# dc32sao.net
KiCad netlist of a schematic drawn in EAGLE
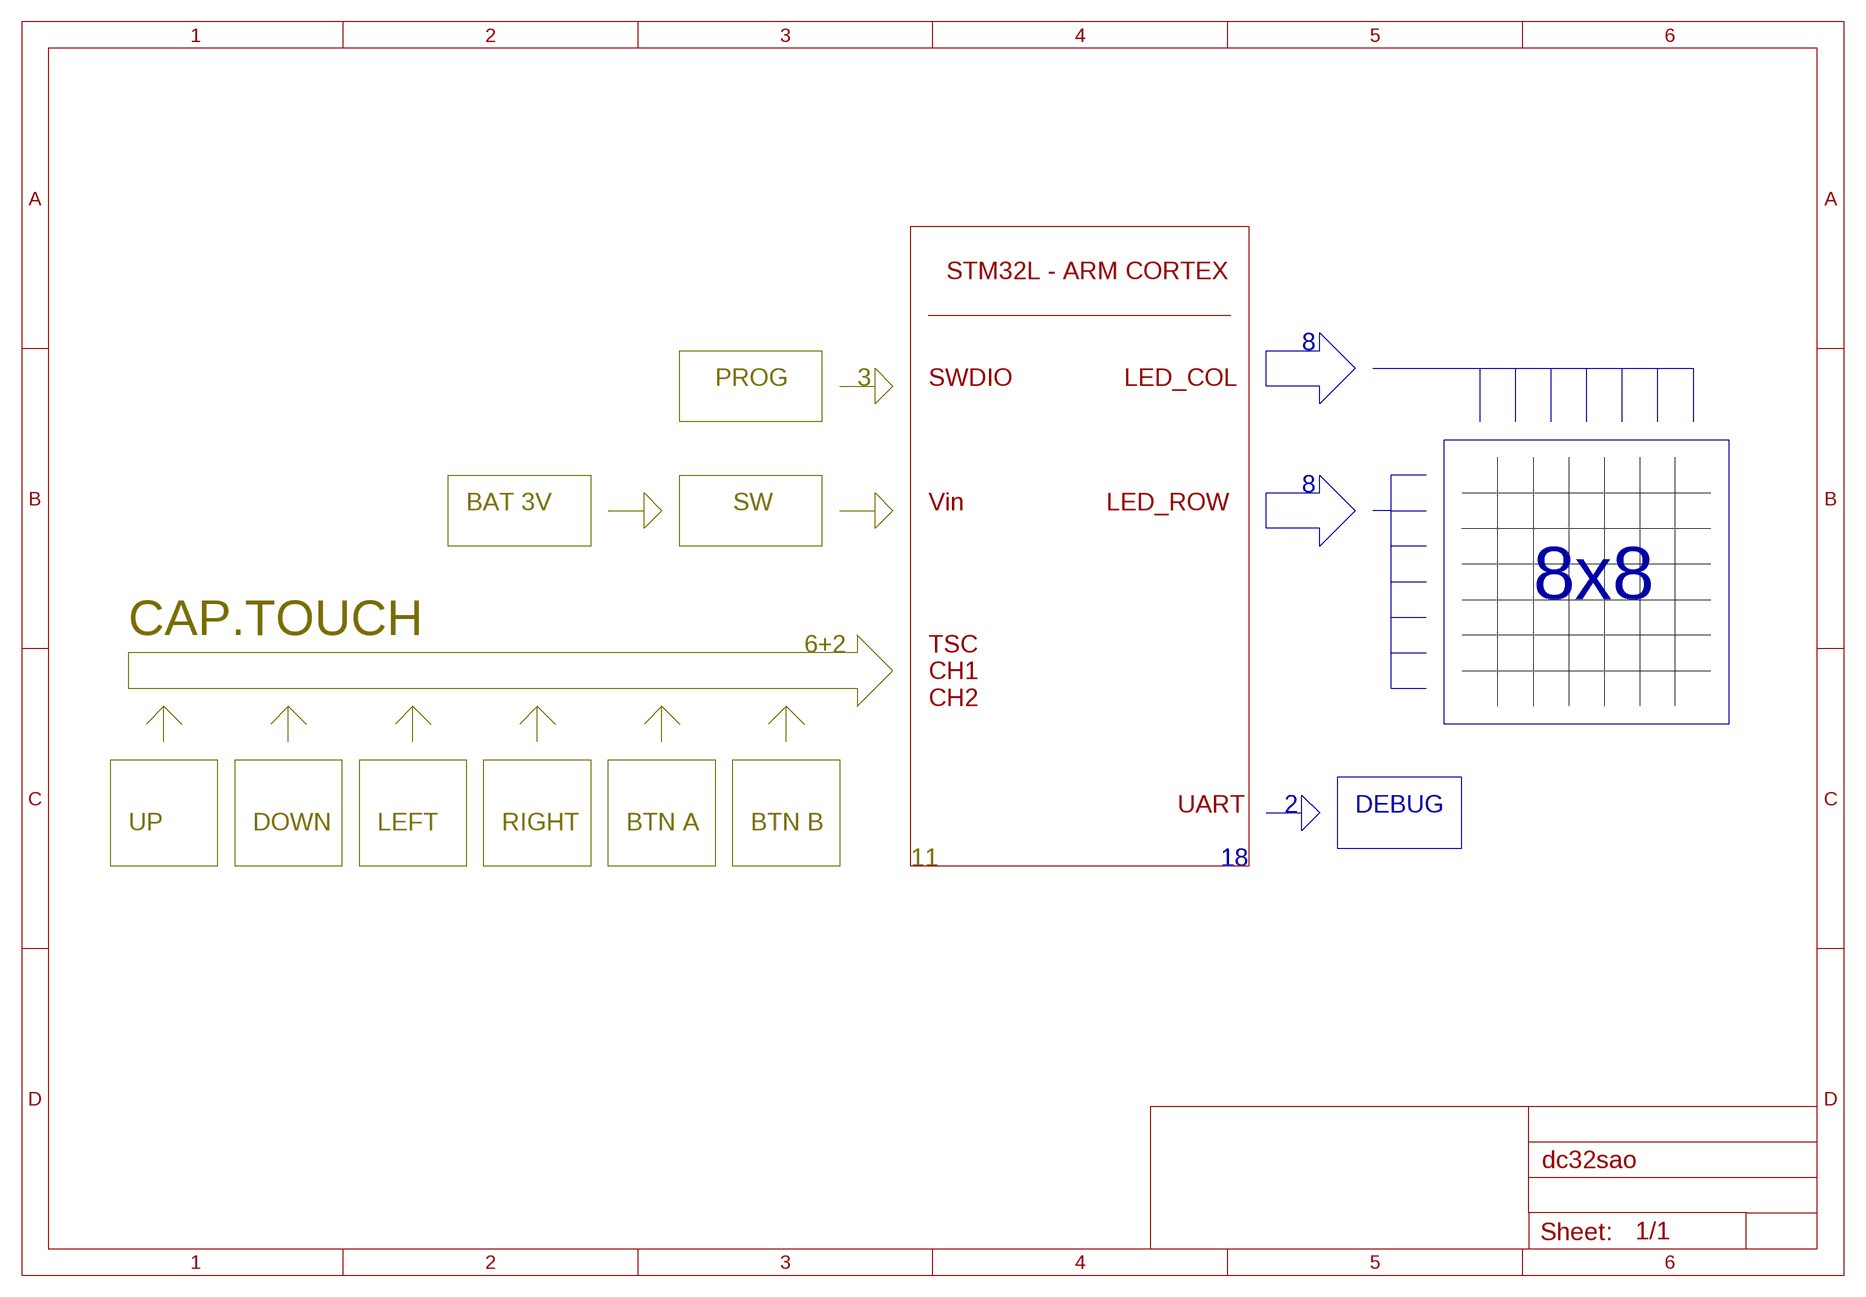
[diagram p0: schematic, sheet 1, part 1 of 2]
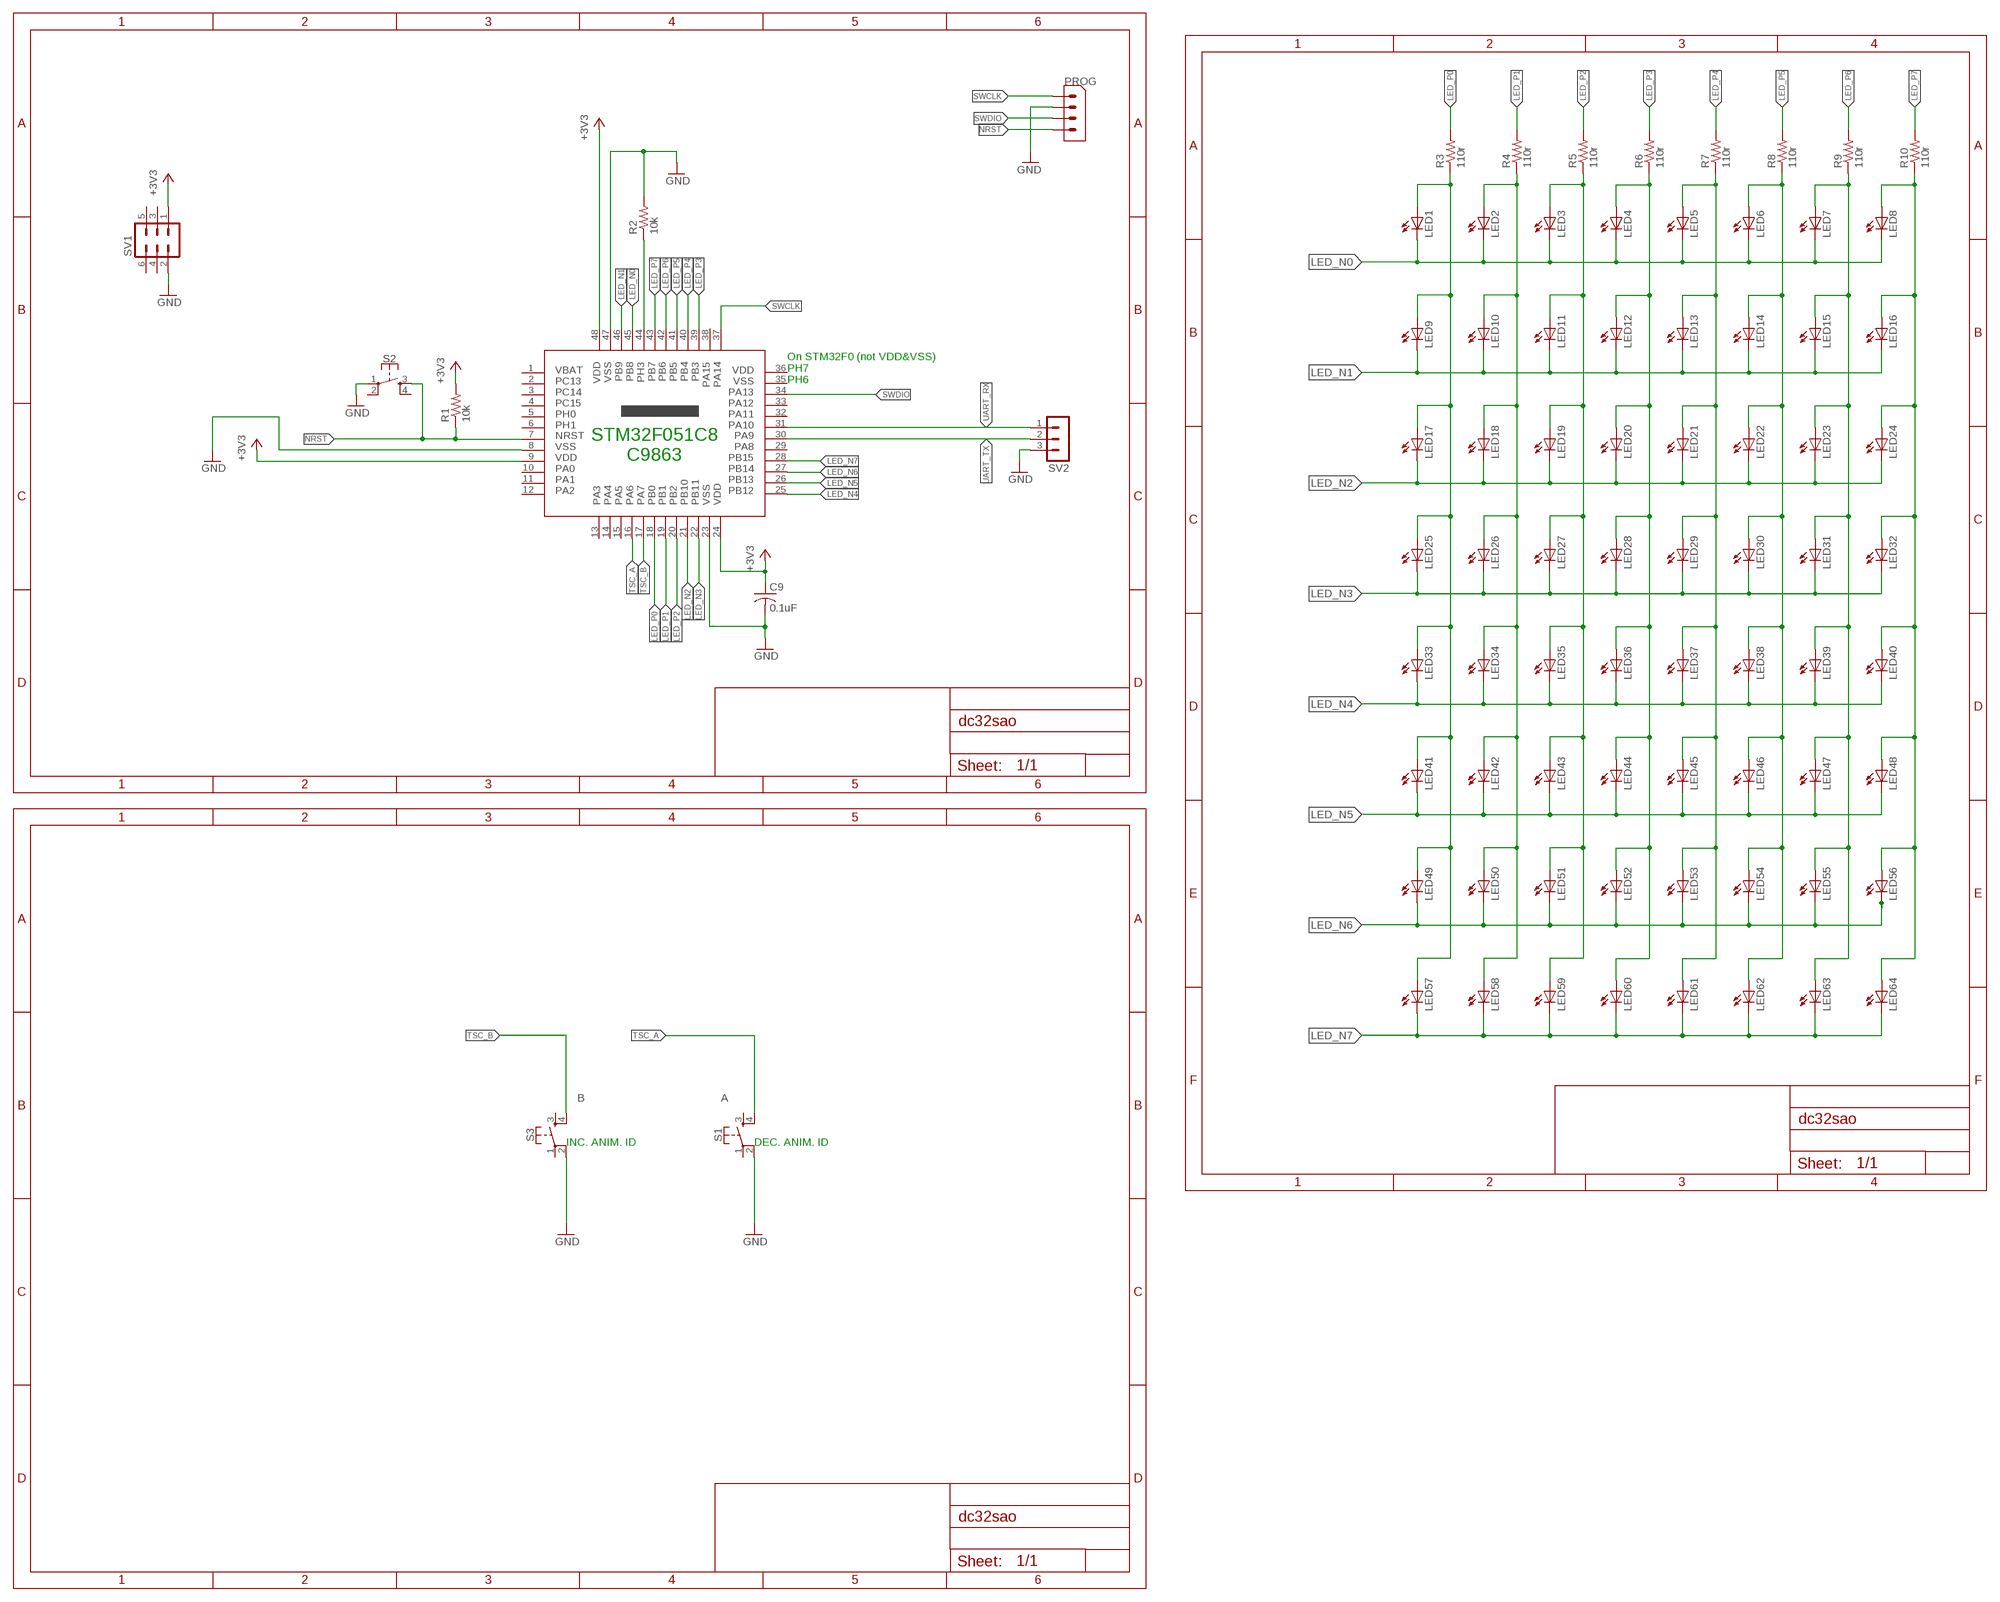
[diagram p1: schematic, sheet 1, part 2 of 2]

(export (version "E")
  (design (tool "Eeschema 10.0.6"))
  (components
    (comp (ref "C9")
      (value "0.1uF")
      (footprint "eagle-import:C0603")
      (libsource (lib "eagle-import") (part "C-USC0603"))
    )
    (comp (ref "LED1")
      (value "LEDCHIP-LED0603")
      (footprint "eagle-import:CHIP-LED0603")
      (libsource (lib "eagle-import") (part "LEDCHIP-LED0603"))
    )
    (comp (ref "LED2")
      (value "LEDCHIP-LED0603")
      (footprint "eagle-import:CHIP-LED0603")
      (libsource (lib "eagle-import") (part "LEDCHIP-LED0603"))
    )
    (comp (ref "LED3")
      (value "LEDCHIP-LED0603")
      (footprint "eagle-import:CHIP-LED0603")
      (libsource (lib "eagle-import") (part "LEDCHIP-LED0603"))
    )
    (comp (ref "LED4")
      (value "LEDCHIP-LED0603")
      (footprint "eagle-import:CHIP-LED0603")
      (libsource (lib "eagle-import") (part "LEDCHIP-LED0603"))
    )
    (comp (ref "LED5")
      (value "LEDCHIP-LED0603")
      (footprint "eagle-import:CHIP-LED0603")
      (libsource (lib "eagle-import") (part "LEDCHIP-LED0603"))
    )
    (comp (ref "LED6")
      (value "LEDCHIP-LED0603")
      (footprint "eagle-import:CHIP-LED0603")
      (libsource (lib "eagle-import") (part "LEDCHIP-LED0603"))
    )
    (comp (ref "LED7")
      (value "LEDCHIP-LED0603")
      (footprint "eagle-import:CHIP-LED0603")
      (libsource (lib "eagle-import") (part "LEDCHIP-LED0603"))
    )
    (comp (ref "LED8")
      (value "LEDCHIP-LED0603")
      (footprint "eagle-import:CHIP-LED0603")
      (libsource (lib "eagle-import") (part "LEDCHIP-LED0603"))
    )
    (comp (ref "LED9")
      (value "LEDCHIP-LED0603")
      (footprint "eagle-import:CHIP-LED0603")
      (libsource (lib "eagle-import") (part "LEDCHIP-LED0603"))
    )
    (comp (ref "LED10")
      (value "LEDCHIP-LED0603")
      (footprint "eagle-import:CHIP-LED0603")
      (libsource (lib "eagle-import") (part "LEDCHIP-LED0603"))
    )
    (comp (ref "LED11")
      (value "LEDCHIP-LED0603")
      (footprint "eagle-import:CHIP-LED0603")
      (libsource (lib "eagle-import") (part "LEDCHIP-LED0603"))
    )
    (comp (ref "LED12")
      (value "LEDCHIP-LED0603")
      (footprint "eagle-import:CHIP-LED0603")
      (libsource (lib "eagle-import") (part "LEDCHIP-LED0603"))
    )
    (comp (ref "LED13")
      (value "LEDCHIP-LED0603")
      (footprint "eagle-import:CHIP-LED0603")
      (libsource (lib "eagle-import") (part "LEDCHIP-LED0603"))
    )
    (comp (ref "LED14")
      (value "LEDCHIP-LED0603")
      (footprint "eagle-import:CHIP-LED0603")
      (libsource (lib "eagle-import") (part "LEDCHIP-LED0603"))
    )
    (comp (ref "LED15")
      (value "LEDCHIP-LED0603")
      (footprint "eagle-import:CHIP-LED0603")
      (libsource (lib "eagle-import") (part "LEDCHIP-LED0603"))
    )
    (comp (ref "LED16")
      (value "LEDCHIP-LED0603")
      (footprint "eagle-import:CHIP-LED0603")
      (libsource (lib "eagle-import") (part "LEDCHIP-LED0603"))
    )
    (comp (ref "LED17")
      (value "LEDCHIP-LED0603")
      (footprint "eagle-import:CHIP-LED0603")
      (libsource (lib "eagle-import") (part "LEDCHIP-LED0603"))
    )
    (comp (ref "LED18")
      (value "LEDCHIP-LED0603")
      (footprint "eagle-import:CHIP-LED0603")
      (libsource (lib "eagle-import") (part "LEDCHIP-LED0603"))
    )
    (comp (ref "LED19")
      (value "LEDCHIP-LED0603")
      (footprint "eagle-import:CHIP-LED0603")
      (libsource (lib "eagle-import") (part "LEDCHIP-LED0603"))
    )
    (comp (ref "LED20")
      (value "LEDCHIP-LED0603")
      (footprint "eagle-import:CHIP-LED0603")
      (libsource (lib "eagle-import") (part "LEDCHIP-LED0603"))
    )
    (comp (ref "LED21")
      (value "LEDCHIP-LED0603")
      (footprint "eagle-import:CHIP-LED0603")
      (libsource (lib "eagle-import") (part "LEDCHIP-LED0603"))
    )
    (comp (ref "LED22")
      (value "LEDCHIP-LED0603")
      (footprint "eagle-import:CHIP-LED0603")
      (libsource (lib "eagle-import") (part "LEDCHIP-LED0603"))
    )
    (comp (ref "LED23")
      (value "LEDCHIP-LED0603")
      (footprint "eagle-import:CHIP-LED0603")
      (libsource (lib "eagle-import") (part "LEDCHIP-LED0603"))
    )
    (comp (ref "LED24")
      (value "LEDCHIP-LED0603")
      (footprint "eagle-import:CHIP-LED0603")
      (libsource (lib "eagle-import") (part "LEDCHIP-LED0603"))
    )
    (comp (ref "LED25")
      (value "LEDCHIP-LED0603")
      (footprint "eagle-import:CHIP-LED0603")
      (libsource (lib "eagle-import") (part "LEDCHIP-LED0603"))
    )
    (comp (ref "LED26")
      (value "LEDCHIP-LED0603")
      (footprint "eagle-import:CHIP-LED0603")
      (libsource (lib "eagle-import") (part "LEDCHIP-LED0603"))
    )
    (comp (ref "LED27")
      (value "LEDCHIP-LED0603")
      (footprint "eagle-import:CHIP-LED0603")
      (libsource (lib "eagle-import") (part "LEDCHIP-LED0603"))
    )
    (comp (ref "LED28")
      (value "LEDCHIP-LED0603")
      (footprint "eagle-import:CHIP-LED0603")
      (libsource (lib "eagle-import") (part "LEDCHIP-LED0603"))
    )
    (comp (ref "LED29")
      (value "LEDCHIP-LED0603")
      (footprint "eagle-import:CHIP-LED0603")
      (libsource (lib "eagle-import") (part "LEDCHIP-LED0603"))
    )
    (comp (ref "LED30")
      (value "LEDCHIP-LED0603")
      (footprint "eagle-import:CHIP-LED0603")
      (libsource (lib "eagle-import") (part "LEDCHIP-LED0603"))
    )
    (comp (ref "LED31")
      (value "LEDCHIP-LED0603")
      (footprint "eagle-import:CHIP-LED0603")
      (libsource (lib "eagle-import") (part "LEDCHIP-LED0603"))
    )
    (comp (ref "LED32")
      (value "LEDCHIP-LED0603")
      (footprint "eagle-import:CHIP-LED0603")
      (libsource (lib "eagle-import") (part "LEDCHIP-LED0603"))
    )
    (comp (ref "LED33")
      (value "LEDCHIP-LED0603")
      (footprint "eagle-import:CHIP-LED0603")
      (libsource (lib "eagle-import") (part "LEDCHIP-LED0603"))
    )
    (comp (ref "LED34")
      (value "LEDCHIP-LED0603")
      (footprint "eagle-import:CHIP-LED0603")
      (libsource (lib "eagle-import") (part "LEDCHIP-LED0603"))
    )
    (comp (ref "LED35")
      (value "LEDCHIP-LED0603")
      (footprint "eagle-import:CHIP-LED0603")
      (libsource (lib "eagle-import") (part "LEDCHIP-LED0603"))
    )
    (comp (ref "LED36")
      (value "LEDCHIP-LED0603")
      (footprint "eagle-import:CHIP-LED0603")
      (libsource (lib "eagle-import") (part "LEDCHIP-LED0603"))
    )
    (comp (ref "LED37")
      (value "LEDCHIP-LED0603")
      (footprint "eagle-import:CHIP-LED0603")
      (libsource (lib "eagle-import") (part "LEDCHIP-LED0603"))
    )
    (comp (ref "LED38")
      (value "LEDCHIP-LED0603")
      (footprint "eagle-import:CHIP-LED0603")
      (libsource (lib "eagle-import") (part "LEDCHIP-LED0603"))
    )
    (comp (ref "LED39")
      (value "LEDCHIP-LED0603")
      (footprint "eagle-import:CHIP-LED0603")
      (libsource (lib "eagle-import") (part "LEDCHIP-LED0603"))
    )
    (comp (ref "LED40")
      (value "LEDCHIP-LED0603")
      (footprint "eagle-import:CHIP-LED0603")
      (libsource (lib "eagle-import") (part "LEDCHIP-LED0603"))
    )
    (comp (ref "LED41")
      (value "LEDCHIP-LED0603")
      (footprint "eagle-import:CHIP-LED0603")
      (libsource (lib "eagle-import") (part "LEDCHIP-LED0603"))
    )
    (comp (ref "LED42")
      (value "LEDCHIP-LED0603")
      (footprint "eagle-import:CHIP-LED0603")
      (libsource (lib "eagle-import") (part "LEDCHIP-LED0603"))
    )
    (comp (ref "LED43")
      (value "LEDCHIP-LED0603")
      (footprint "eagle-import:CHIP-LED0603")
      (libsource (lib "eagle-import") (part "LEDCHIP-LED0603"))
    )
    (comp (ref "LED44")
      (value "LEDCHIP-LED0603")
      (footprint "eagle-import:CHIP-LED0603")
      (libsource (lib "eagle-import") (part "LEDCHIP-LED0603"))
    )
    (comp (ref "LED45")
      (value "LEDCHIP-LED0603")
      (footprint "eagle-import:CHIP-LED0603")
      (libsource (lib "eagle-import") (part "LEDCHIP-LED0603"))
    )
    (comp (ref "LED46")
      (value "LEDCHIP-LED0603")
      (footprint "eagle-import:CHIP-LED0603")
      (libsource (lib "eagle-import") (part "LEDCHIP-LED0603"))
    )
    (comp (ref "LED47")
      (value "LEDCHIP-LED0603")
      (footprint "eagle-import:CHIP-LED0603")
      (libsource (lib "eagle-import") (part "LEDCHIP-LED0603"))
    )
    (comp (ref "LED48")
      (value "LEDCHIP-LED0603")
      (footprint "eagle-import:CHIP-LED0603")
      (libsource (lib "eagle-import") (part "LEDCHIP-LED0603"))
    )
    (comp (ref "LED49")
      (value "LEDCHIP-LED0603")
      (footprint "eagle-import:CHIP-LED0603")
      (libsource (lib "eagle-import") (part "LEDCHIP-LED0603"))
    )
    (comp (ref "LED50")
      (value "LEDCHIP-LED0603")
      (footprint "eagle-import:CHIP-LED0603")
      (libsource (lib "eagle-import") (part "LEDCHIP-LED0603"))
    )
    (comp (ref "LED51")
      (value "LEDCHIP-LED0603")
      (footprint "eagle-import:CHIP-LED0603")
      (libsource (lib "eagle-import") (part "LEDCHIP-LED0603"))
    )
    (comp (ref "LED52")
      (value "LEDCHIP-LED0603")
      (footprint "eagle-import:CHIP-LED0603")
      (libsource (lib "eagle-import") (part "LEDCHIP-LED0603"))
    )
    (comp (ref "LED53")
      (value "LEDCHIP-LED0603")
      (footprint "eagle-import:CHIP-LED0603")
      (libsource (lib "eagle-import") (part "LEDCHIP-LED0603"))
    )
    (comp (ref "LED54")
      (value "LEDCHIP-LED0603")
      (footprint "eagle-import:CHIP-LED0603")
      (libsource (lib "eagle-import") (part "LEDCHIP-LED0603"))
    )
    (comp (ref "LED55")
      (value "LEDCHIP-LED0603")
      (footprint "eagle-import:CHIP-LED0603")
      (libsource (lib "eagle-import") (part "LEDCHIP-LED0603"))
    )
    (comp (ref "LED56")
      (value "LEDCHIP-LED0603")
      (footprint "eagle-import:CHIP-LED0603")
      (libsource (lib "eagle-import") (part "LEDCHIP-LED0603"))
    )
    (comp (ref "LED57")
      (value "LEDCHIP-LED0603")
      (footprint "eagle-import:CHIP-LED0603")
      (libsource (lib "eagle-import") (part "LEDCHIP-LED0603"))
    )
    (comp (ref "LED58")
      (value "LEDCHIP-LED0603")
      (footprint "eagle-import:CHIP-LED0603")
      (libsource (lib "eagle-import") (part "LEDCHIP-LED0603"))
    )
    (comp (ref "LED59")
      (value "LEDCHIP-LED0603")
      (footprint "eagle-import:CHIP-LED0603")
      (libsource (lib "eagle-import") (part "LEDCHIP-LED0603"))
    )
    (comp (ref "LED60")
      (value "LEDCHIP-LED0603")
      (footprint "eagle-import:CHIP-LED0603")
      (libsource (lib "eagle-import") (part "LEDCHIP-LED0603"))
    )
    (comp (ref "LED61")
      (value "LEDCHIP-LED0603")
      (footprint "eagle-import:CHIP-LED0603")
      (libsource (lib "eagle-import") (part "LEDCHIP-LED0603"))
    )
    (comp (ref "LED62")
      (value "LEDCHIP-LED0603")
      (footprint "eagle-import:CHIP-LED0603")
      (libsource (lib "eagle-import") (part "LEDCHIP-LED0603"))
    )
    (comp (ref "LED63")
      (value "LEDCHIP-LED0603")
      (footprint "eagle-import:CHIP-LED0603")
      (libsource (lib "eagle-import") (part "LEDCHIP-LED0603"))
    )
    (comp (ref "LED64")
      (value "LEDCHIP-LED0603")
      (footprint "eagle-import:CHIP-LED0603")
      (libsource (lib "eagle-import") (part "LEDCHIP-LED0603"))
    )
    (comp (ref "PROG")
      (value "4-PIN-1.25MM")
      (footprint "eagle-import:4-PIN-1.25MM")
      (libsource (lib "eagle-import") (part "4-PIN-1.25MM"))
    )
    (comp (ref "R1")
      (value "10k")
      (footprint "eagle-import:R0603")
      (libsource (lib "eagle-import") (part "R-US_R0603"))
    )
    (comp (ref "R2")
      (value "10k")
      (footprint "eagle-import:R0603")
      (libsource (lib "eagle-import") (part "R-US_R0603"))
    )
    (comp (ref "R3")
      (value "110r")
      (footprint "eagle-import:R0603")
      (libsource (lib "eagle-import") (part "R-US_R0603"))
    )
    (comp (ref "R4")
      (value "110r")
      (footprint "eagle-import:R0603")
      (libsource (lib "eagle-import") (part "R-US_R0603"))
    )
    (comp (ref "R5")
      (value "110r")
      (footprint "eagle-import:R0603")
      (libsource (lib "eagle-import") (part "R-US_R0603"))
    )
    (comp (ref "R6")
      (value "110r")
      (footprint "eagle-import:R0603")
      (libsource (lib "eagle-import") (part "R-US_R0603"))
    )
    (comp (ref "R7")
      (value "110r")
      (footprint "eagle-import:R0603")
      (libsource (lib "eagle-import") (part "R-US_R0603"))
    )
    (comp (ref "R8")
      (value "110r")
      (footprint "eagle-import:R0603")
      (libsource (lib "eagle-import") (part "R-US_R0603"))
    )
    (comp (ref "R9")
      (value "110r")
      (footprint "eagle-import:R0603")
      (libsource (lib "eagle-import") (part "R-US_R0603"))
    )
    (comp (ref "R10")
      (value "110r")
      (footprint "eagle-import:R0603")
      (libsource (lib "eagle-import") (part "R-US_R0603"))
    )
    (comp (ref "S1")
      (value "MOMENTARY-SWITCH-SPST-2-SMD-5.2MM")
      (footprint "eagle-import:TACTILE_SWITCH_SMD_5.2MM")
      (libsource (lib "eagle-import") (part "MOMENTARY-SWITCH-SPST-2-SMD-5.2MM"))
    )
    (comp (ref "S2")
      (value "MOMENTARY-SWITCH-SPST-2-SMD-5.2MM")
      (footprint "eagle-import:TACTILE_SWITCH_SMD_5.2MM")
      (libsource (lib "eagle-import") (part "MOMENTARY-SWITCH-SPST-2-SMD-5.2MM"))
    )
    (comp (ref "S3")
      (value "MOMENTARY-SWITCH-SPST-2-SMD-5.2MM")
      (footprint "eagle-import:TACTILE_SWITCH_SMD_5.2MM")
      (libsource (lib "eagle-import") (part "MOMENTARY-SWITCH-SPST-2-SMD-5.2MM"))
    )
    (comp (ref "SV1")
      (value "MA03-2")
      (footprint "eagle-import:MA03-2")
      (libsource (lib "eagle-import") (part "MA03-2"))
    )
    (comp (ref "SV2")
      (value "MA03-1")
      (footprint "eagle-import:MA03-1")
      (libsource (lib "eagle-import") (part "MA03-1"))
    )
    (comp (ref "U$2")
      (value "STM32L431CC")
      (footprint "eagle-import:QFP50P900X900X160-48")
      (libsource (lib "eagle-import") (part "STM32L431CC"))
    )
  )
  (nets
    (net (code "1") (name "+3V3") (class "Default")
      (node (ref "C9") (pin "1") (pinfunction "1_1") (pintype "passive"))
      (node (ref "R1") (pin "2") (pinfunction "2_2") (pintype "passive"))
      (node (ref "SV1") (pin "1") (pinfunction "1_1") (pintype "passive"))
      (node (ref "U$2") (pin "24") (pinfunction "P$24_24") (pintype "bidirectional"))
      (node (ref "U$2") (pin "48") (pinfunction "P$48_48") (pintype "bidirectional"))
      (node (ref "U$2") (pin "9") (pinfunction "P$9_9") (pintype "bidirectional"))
    )
    (net (code "2") (name "GND") (class "Default")
      (node (ref "C9") (pin "2") (pinfunction "2_2") (pintype "passive"))
      (node (ref "PROG") (pin "P$3") (pinfunction "2_P$3") (pintype "bidirectional"))
      (node (ref "R2") (pin "2") (pinfunction "2_2") (pintype "passive"))
      (node (ref "S1") (pin "2") (pinfunction "2_2") (pintype "passive"))
      (node (ref "S2") (pin "1") (pinfunction "1_1") (pintype "passive"))
      (node (ref "S3") (pin "2") (pinfunction "2_2") (pintype "passive"))
      (node (ref "SV1") (pin "2") (pinfunction "2_2") (pintype "passive"))
      (node (ref "SV2") (pin "3") (pinfunction "3_3") (pintype "passive"))
      (node (ref "U$2") (pin "23") (pinfunction "P$23_23") (pintype "bidirectional"))
      (node (ref "U$2") (pin "47") (pinfunction "P$47_47") (pintype "bidirectional"))
      (node (ref "U$2") (pin "8") (pinfunction "P$8_8") (pintype "bidirectional"))
    )
    (net (code "3") (name "LED_N0") (class "Default")
      (node (ref "LED1") (pin "C") (pinfunction "C_C") (pintype "passive"))
      (node (ref "LED2") (pin "C") (pinfunction "C_C") (pintype "passive"))
      (node (ref "LED3") (pin "C") (pinfunction "C_C") (pintype "passive"))
      (node (ref "LED4") (pin "C") (pinfunction "C_C") (pintype "passive"))
      (node (ref "LED5") (pin "C") (pinfunction "C_C") (pintype "passive"))
      (node (ref "LED6") (pin "C") (pinfunction "C_C") (pintype "passive"))
      (node (ref "LED7") (pin "C") (pinfunction "C_C") (pintype "passive"))
      (node (ref "LED8") (pin "C") (pinfunction "C_C") (pintype "passive"))
      (node (ref "U$2") (pin "45") (pinfunction "P$45_45") (pintype "bidirectional"))
    )
    (net (code "4") (name "LED_N1") (class "Default")
      (node (ref "LED10") (pin "C") (pinfunction "C_C") (pintype "passive"))
      (node (ref "LED11") (pin "C") (pinfunction "C_C") (pintype "passive"))
      (node (ref "LED12") (pin "C") (pinfunction "C_C") (pintype "passive"))
      (node (ref "LED13") (pin "C") (pinfunction "C_C") (pintype "passive"))
      (node (ref "LED14") (pin "C") (pinfunction "C_C") (pintype "passive"))
      (node (ref "LED15") (pin "C") (pinfunction "C_C") (pintype "passive"))
      (node (ref "LED16") (pin "C") (pinfunction "C_C") (pintype "passive"))
      (node (ref "LED9") (pin "C") (pinfunction "C_C") (pintype "passive"))
      (node (ref "U$2") (pin "46") (pinfunction "P$46_46") (pintype "bidirectional"))
    )
    (net (code "5") (name "LED_N2") (class "Default")
      (node (ref "LED17") (pin "C") (pinfunction "C_C") (pintype "passive"))
      (node (ref "LED18") (pin "C") (pinfunction "C_C") (pintype "passive"))
      (node (ref "LED19") (pin "C") (pinfunction "C_C") (pintype "passive"))
      (node (ref "LED20") (pin "C") (pinfunction "C_C") (pintype "passive"))
      (node (ref "LED21") (pin "C") (pinfunction "C_C") (pintype "passive"))
      (node (ref "LED22") (pin "C") (pinfunction "C_C") (pintype "passive"))
      (node (ref "LED23") (pin "C") (pinfunction "C_C") (pintype "passive"))
      (node (ref "LED24") (pin "C") (pinfunction "C_C") (pintype "passive"))
      (node (ref "U$2") (pin "21") (pinfunction "P$21_21") (pintype "bidirectional"))
    )
    (net (code "6") (name "LED_N3") (class "Default")
      (node (ref "LED25") (pin "C") (pinfunction "C_C") (pintype "passive"))
      (node (ref "LED26") (pin "C") (pinfunction "C_C") (pintype "passive"))
      (node (ref "LED27") (pin "C") (pinfunction "C_C") (pintype "passive"))
      (node (ref "LED28") (pin "C") (pinfunction "C_C") (pintype "passive"))
      (node (ref "LED29") (pin "C") (pinfunction "C_C") (pintype "passive"))
      (node (ref "LED30") (pin "C") (pinfunction "C_C") (pintype "passive"))
      (node (ref "LED31") (pin "C") (pinfunction "C_C") (pintype "passive"))
      (node (ref "LED32") (pin "C") (pinfunction "C_C") (pintype "passive"))
      (node (ref "U$2") (pin "22") (pinfunction "P$22_22") (pintype "bidirectional"))
    )
    (net (code "7") (name "LED_N4") (class "Default")
      (node (ref "LED33") (pin "C") (pinfunction "C_C") (pintype "passive"))
      (node (ref "LED34") (pin "C") (pinfunction "C_C") (pintype "passive"))
      (node (ref "LED35") (pin "C") (pinfunction "C_C") (pintype "passive"))
      (node (ref "LED36") (pin "C") (pinfunction "C_C") (pintype "passive"))
      (node (ref "LED37") (pin "C") (pinfunction "C_C") (pintype "passive"))
      (node (ref "LED38") (pin "C") (pinfunction "C_C") (pintype "passive"))
      (node (ref "LED39") (pin "C") (pinfunction "C_C") (pintype "passive"))
      (node (ref "LED40") (pin "C") (pinfunction "C_C") (pintype "passive"))
      (node (ref "U$2") (pin "25") (pinfunction "P$25_25") (pintype "bidirectional"))
    )
    (net (code "8") (name "LED_N5") (class "Default")
      (node (ref "LED41") (pin "C") (pinfunction "C_C") (pintype "passive"))
      (node (ref "LED42") (pin "C") (pinfunction "C_C") (pintype "passive"))
      (node (ref "LED43") (pin "C") (pinfunction "C_C") (pintype "passive"))
      (node (ref "LED44") (pin "C") (pinfunction "C_C") (pintype "passive"))
      (node (ref "LED45") (pin "C") (pinfunction "C_C") (pintype "passive"))
      (node (ref "LED46") (pin "C") (pinfunction "C_C") (pintype "passive"))
      (node (ref "LED47") (pin "C") (pinfunction "C_C") (pintype "passive"))
      (node (ref "LED48") (pin "C") (pinfunction "C_C") (pintype "passive"))
      (node (ref "U$2") (pin "26") (pinfunction "P$26_26") (pintype "bidirectional"))
    )
    (net (code "9") (name "LED_N6") (class "Default")
      (node (ref "LED49") (pin "C") (pinfunction "C_C") (pintype "passive"))
      (node (ref "LED50") (pin "C") (pinfunction "C_C") (pintype "passive"))
      (node (ref "LED51") (pin "C") (pinfunction "C_C") (pintype "passive"))
      (node (ref "LED52") (pin "C") (pinfunction "C_C") (pintype "passive"))
      (node (ref "LED53") (pin "C") (pinfunction "C_C") (pintype "passive"))
      (node (ref "LED54") (pin "C") (pinfunction "C_C") (pintype "passive"))
      (node (ref "LED55") (pin "C") (pinfunction "C_C") (pintype "passive"))
      (node (ref "LED56") (pin "C") (pinfunction "C_C") (pintype "passive"))
      (node (ref "U$2") (pin "27") (pinfunction "P$27_27") (pintype "bidirectional"))
    )
    (net (code "10") (name "LED_N7") (class "Default")
      (node (ref "LED57") (pin "C") (pinfunction "C_C") (pintype "passive"))
      (node (ref "LED58") (pin "C") (pinfunction "C_C") (pintype "passive"))
      (node (ref "LED59") (pin "C") (pinfunction "C_C") (pintype "passive"))
      (node (ref "LED60") (pin "C") (pinfunction "C_C") (pintype "passive"))
      (node (ref "LED61") (pin "C") (pinfunction "C_C") (pintype "passive"))
      (node (ref "LED62") (pin "C") (pinfunction "C_C") (pintype "passive"))
      (node (ref "LED63") (pin "C") (pinfunction "C_C") (pintype "passive"))
      (node (ref "LED64") (pin "C") (pinfunction "C_C") (pintype "passive"))
      (node (ref "U$2") (pin "28") (pinfunction "P$28_28") (pintype "bidirectional"))
    )
    (net (code "11") (name "LED_P0") (class "Default")
      (node (ref "R3") (pin "2") (pinfunction "2_2") (pintype "passive"))
      (node (ref "U$2") (pin "18") (pinfunction "P$18_18") (pintype "bidirectional"))
    )
    (net (code "12") (name "LED_P1") (class "Default")
      (node (ref "R4") (pin "2") (pinfunction "2_2") (pintype "passive"))
      (node (ref "U$2") (pin "19") (pinfunction "P$19_19") (pintype "bidirectional"))
    )
    (net (code "13") (name "LED_P2") (class "Default")
      (node (ref "R5") (pin "2") (pinfunction "2_2") (pintype "passive"))
      (node (ref "U$2") (pin "20") (pinfunction "P$20_20") (pintype "bidirectional"))
    )
    (net (code "14") (name "LED_P3") (class "Default")
      (node (ref "R6") (pin "2") (pinfunction "2_2") (pintype "passive"))
      (node (ref "U$2") (pin "39") (pinfunction "P$39_39") (pintype "bidirectional"))
    )
    (net (code "15") (name "LED_P4") (class "Default")
      (node (ref "R7") (pin "2") (pinfunction "2_2") (pintype "passive"))
      (node (ref "U$2") (pin "40") (pinfunction "P$40_40") (pintype "bidirectional"))
    )
    (net (code "16") (name "LED_P5") (class "Default")
      (node (ref "R8") (pin "2") (pinfunction "2_2") (pintype "passive"))
      (node (ref "U$2") (pin "41") (pinfunction "P$41_41") (pintype "bidirectional"))
    )
    (net (code "17") (name "LED_P6") (class "Default")
      (node (ref "R9") (pin "2") (pinfunction "2_2") (pintype "passive"))
      (node (ref "U$2") (pin "42") (pinfunction "P$42_42") (pintype "bidirectional"))
    )
    (net (code "18") (name "LED_P7") (class "Default")
      (node (ref "R10") (pin "2") (pinfunction "2_2") (pintype "passive"))
      (node (ref "U$2") (pin "43") (pinfunction "P$43_43") (pintype "bidirectional"))
    )
    (net (code "19") (name "NRST") (class "Default")
      (node (ref "PROG") (pin "P$1") (pinfunction "4_P$1") (pintype "bidirectional"))
      (node (ref "R1") (pin "1") (pinfunction "1_1") (pintype "passive"))
      (node (ref "S2") (pin "3") (pinfunction "3_3") (pintype "passive"))
      (node (ref "U$2") (pin "7") (pinfunction "P$7_7") (pintype "bidirectional"))
    )
    (net (code "20") (name "Net-(LED1-PadA)") (class "Default")
      (node (ref "LED1") (pin "A") (pinfunction "A_A") (pintype "passive"))
      (node (ref "LED17") (pin "A") (pinfunction "A_A") (pintype "passive"))
      (node (ref "LED25") (pin "A") (pinfunction "A_A") (pintype "passive"))
      (node (ref "LED33") (pin "A") (pinfunction "A_A") (pintype "passive"))
      (node (ref "LED41") (pin "A") (pinfunction "A_A") (pintype "passive"))
      (node (ref "LED49") (pin "A") (pinfunction "A_A") (pintype "passive"))
      (node (ref "LED57") (pin "A") (pinfunction "A_A") (pintype "passive"))
      (node (ref "LED9") (pin "A") (pinfunction "A_A") (pintype "passive"))
      (node (ref "R3") (pin "1") (pinfunction "1_1") (pintype "passive"))
    )
    (net (code "21") (name "Net-(LED10-PadA)") (class "Default")
      (node (ref "LED10") (pin "A") (pinfunction "A_A") (pintype "passive"))
      (node (ref "LED18") (pin "A") (pinfunction "A_A") (pintype "passive"))
      (node (ref "LED2") (pin "A") (pinfunction "A_A") (pintype "passive"))
      (node (ref "LED26") (pin "A") (pinfunction "A_A") (pintype "passive"))
      (node (ref "LED34") (pin "A") (pinfunction "A_A") (pintype "passive"))
      (node (ref "LED42") (pin "A") (pinfunction "A_A") (pintype "passive"))
      (node (ref "LED50") (pin "A") (pinfunction "A_A") (pintype "passive"))
      (node (ref "LED58") (pin "A") (pinfunction "A_A") (pintype "passive"))
      (node (ref "R4") (pin "1") (pinfunction "1_1") (pintype "passive"))
    )
    (net (code "22") (name "Net-(LED11-PadA)") (class "Default")
      (node (ref "LED11") (pin "A") (pinfunction "A_A") (pintype "passive"))
      (node (ref "LED19") (pin "A") (pinfunction "A_A") (pintype "passive"))
      (node (ref "LED27") (pin "A") (pinfunction "A_A") (pintype "passive"))
      (node (ref "LED3") (pin "A") (pinfunction "A_A") (pintype "passive"))
      (node (ref "LED35") (pin "A") (pinfunction "A_A") (pintype "passive"))
      (node (ref "LED43") (pin "A") (pinfunction "A_A") (pintype "passive"))
      (node (ref "LED51") (pin "A") (pinfunction "A_A") (pintype "passive"))
      (node (ref "LED59") (pin "A") (pinfunction "A_A") (pintype "passive"))
      (node (ref "R5") (pin "1") (pinfunction "1_1") (pintype "passive"))
    )
    (net (code "23") (name "Net-(LED12-PadA)") (class "Default")
      (node (ref "LED12") (pin "A") (pinfunction "A_A") (pintype "passive"))
      (node (ref "LED20") (pin "A") (pinfunction "A_A") (pintype "passive"))
      (node (ref "LED28") (pin "A") (pinfunction "A_A") (pintype "passive"))
      (node (ref "LED36") (pin "A") (pinfunction "A_A") (pintype "passive"))
      (node (ref "LED4") (pin "A") (pinfunction "A_A") (pintype "passive"))
      (node (ref "LED44") (pin "A") (pinfunction "A_A") (pintype "passive"))
      (node (ref "LED52") (pin "A") (pinfunction "A_A") (pintype "passive"))
      (node (ref "LED60") (pin "A") (pinfunction "A_A") (pintype "passive"))
      (node (ref "R6") (pin "1") (pinfunction "1_1") (pintype "passive"))
    )
    (net (code "24") (name "Net-(LED13-PadA)") (class "Default")
      (node (ref "LED13") (pin "A") (pinfunction "A_A") (pintype "passive"))
      (node (ref "LED21") (pin "A") (pinfunction "A_A") (pintype "passive"))
      (node (ref "LED29") (pin "A") (pinfunction "A_A") (pintype "passive"))
      (node (ref "LED37") (pin "A") (pinfunction "A_A") (pintype "passive"))
      (node (ref "LED45") (pin "A") (pinfunction "A_A") (pintype "passive"))
      (node (ref "LED5") (pin "A") (pinfunction "A_A") (pintype "passive"))
      (node (ref "LED53") (pin "A") (pinfunction "A_A") (pintype "passive"))
      (node (ref "LED61") (pin "A") (pinfunction "A_A") (pintype "passive"))
      (node (ref "R7") (pin "1") (pinfunction "1_1") (pintype "passive"))
    )
    (net (code "25") (name "Net-(LED14-PadA)") (class "Default")
      (node (ref "LED14") (pin "A") (pinfunction "A_A") (pintype "passive"))
      (node (ref "LED22") (pin "A") (pinfunction "A_A") (pintype "passive"))
      (node (ref "LED30") (pin "A") (pinfunction "A_A") (pintype "passive"))
      (node (ref "LED38") (pin "A") (pinfunction "A_A") (pintype "passive"))
      (node (ref "LED46") (pin "A") (pinfunction "A_A") (pintype "passive"))
      (node (ref "LED54") (pin "A") (pinfunction "A_A") (pintype "passive"))
      (node (ref "LED6") (pin "A") (pinfunction "A_A") (pintype "passive"))
      (node (ref "LED62") (pin "A") (pinfunction "A_A") (pintype "passive"))
      (node (ref "R8") (pin "1") (pinfunction "1_1") (pintype "passive"))
    )
    (net (code "26") (name "Net-(LED15-PadA)") (class "Default")
      (node (ref "LED15") (pin "A") (pinfunction "A_A") (pintype "passive"))
      (node (ref "LED23") (pin "A") (pinfunction "A_A") (pintype "passive"))
      (node (ref "LED31") (pin "A") (pinfunction "A_A") (pintype "passive"))
      (node (ref "LED39") (pin "A") (pinfunction "A_A") (pintype "passive"))
      (node (ref "LED47") (pin "A") (pinfunction "A_A") (pintype "passive"))
      (node (ref "LED55") (pin "A") (pinfunction "A_A") (pintype "passive"))
      (node (ref "LED63") (pin "A") (pinfunction "A_A") (pintype "passive"))
      (node (ref "LED7") (pin "A") (pinfunction "A_A") (pintype "passive"))
      (node (ref "R9") (pin "1") (pinfunction "1_1") (pintype "passive"))
    )
    (net (code "27") (name "Net-(LED16-PadA)") (class "Default")
      (node (ref "LED16") (pin "A") (pinfunction "A_A") (pintype "passive"))
      (node (ref "LED24") (pin "A") (pinfunction "A_A") (pintype "passive"))
      (node (ref "LED32") (pin "A") (pinfunction "A_A") (pintype "passive"))
      (node (ref "LED40") (pin "A") (pinfunction "A_A") (pintype "passive"))
      (node (ref "LED48") (pin "A") (pinfunction "A_A") (pintype "passive"))
      (node (ref "LED56") (pin "A") (pinfunction "A_A") (pintype "passive"))
      (node (ref "LED64") (pin "A") (pinfunction "A_A") (pintype "passive"))
      (node (ref "LED8") (pin "A") (pinfunction "A_A") (pintype "passive"))
      (node (ref "R10") (pin "1") (pinfunction "1_1") (pintype "passive"))
    )
    (net (code "28") (name "Net-(U$2-P$44)") (class "Default")
      (node (ref "R2") (pin "1") (pinfunction "1_1") (pintype "passive"))
      (node (ref "U$2") (pin "44") (pinfunction "P$44_44") (pintype "bidirectional"))
    )
    (net (code "29") (name "SWCLK") (class "Default")
      (node (ref "PROG") (pin "P$4") (pinfunction "1_P$4") (pintype "bidirectional"))
      (node (ref "U$2") (pin "37") (pinfunction "P$37_37") (pintype "bidirectional"))
    )
    (net (code "30") (name "SWDIO") (class "Default")
      (node (ref "PROG") (pin "P$2") (pinfunction "3_P$2") (pintype "bidirectional"))
      (node (ref "U$2") (pin "34") (pinfunction "P$34_34") (pintype "bidirectional"))
    )
    (net (code "31") (name "TSC_A") (class "Default")
      (node (ref "S1") (pin "4") (pinfunction "4_4") (pintype "passive"))
      (node (ref "U$2") (pin "16") (pinfunction "P$16_16") (pintype "bidirectional"))
    )
    (net (code "32") (name "TSC_B") (class "Default")
      (node (ref "S3") (pin "4") (pinfunction "4_4") (pintype "passive"))
      (node (ref "U$2") (pin "17") (pinfunction "P$17_17") (pintype "bidirectional"))
    )
    (net (code "33") (name "UART_RX") (class "Default")
      (node (ref "SV2") (pin "1") (pinfunction "1_1") (pintype "passive"))
      (node (ref "U$2") (pin "31") (pinfunction "P$31_31") (pintype "bidirectional"))
    )
    (net (code "34") (name "UART_TX") (class "Default")
      (node (ref "SV2") (pin "2") (pinfunction "2_2") (pintype "passive"))
      (node (ref "U$2") (pin "30") (pinfunction "P$30_30") (pintype "bidirectional"))
    )
    (net (code "35") (name "unconnected-(S1-Pad1)") (class "Default")
      (node (ref "S1") (pin "1") (pinfunction "1_1") (pintype "passive"))
    )
    (net (code "36") (name "unconnected-(S1-Pad3)") (class "Default")
      (node (ref "S1") (pin "3") (pinfunction "3_3") (pintype "passive"))
    )
    (net (code "37") (name "unconnected-(S2-Pad2)") (class "Default")
      (node (ref "S2") (pin "2") (pinfunction "2_2") (pintype "passive"))
    )
    (net (code "38") (name "unconnected-(S2-Pad4)") (class "Default")
      (node (ref "S2") (pin "4") (pinfunction "4_4") (pintype "passive"))
    )
    (net (code "39") (name "unconnected-(S3-Pad1)") (class "Default")
      (node (ref "S3") (pin "1") (pinfunction "1_1") (pintype "passive"))
    )
    (net (code "40") (name "unconnected-(S3-Pad3)") (class "Default")
      (node (ref "S3") (pin "3") (pinfunction "3_3") (pintype "passive"))
    )
    (net (code "41") (name "unconnected-(SV1-Pad3)") (class "Default")
      (node (ref "SV1") (pin "3") (pinfunction "3_3") (pintype "passive"))
    )
    (net (code "42") (name "unconnected-(SV1-Pad4)") (class "Default")
      (node (ref "SV1") (pin "4") (pinfunction "4_4") (pintype "passive"))
    )
    (net (code "43") (name "unconnected-(SV1-Pad5)") (class "Default")
      (node (ref "SV1") (pin "5") (pinfunction "5_5") (pintype "passive"))
    )
    (net (code "44") (name "unconnected-(SV1-Pad6)") (class "Default")
      (node (ref "SV1") (pin "6") (pinfunction "6_6") (pintype "passive"))
    )
    (net (code "45") (name "unconnected-(U$2-P$1-Pad1)") (class "Default")
      (node (ref "U$2") (pin "1") (pinfunction "P$1_1") (pintype "bidirectional"))
    )
    (net (code "46") (name "unconnected-(U$2-P$2-Pad2)") (class "Default")
      (node (ref "U$2") (pin "2") (pinfunction "P$2_2") (pintype "bidirectional"))
    )
    (net (code "47") (name "unconnected-(U$2-P$3-Pad3)") (class "Default")
      (node (ref "U$2") (pin "3") (pinfunction "P$3_3") (pintype "bidirectional"))
    )
    (net (code "48") (name "unconnected-(U$2-P$4-Pad4)") (class "Default")
      (node (ref "U$2") (pin "4") (pinfunction "P$4_4") (pintype "bidirectional"))
    )
    (net (code "49") (name "unconnected-(U$2-P$5-Pad5)") (class "Default")
      (node (ref "U$2") (pin "5") (pinfunction "P$5_5") (pintype "bidirectional"))
    )
    (net (code "50") (name "unconnected-(U$2-P$6-Pad6)") (class "Default")
      (node (ref "U$2") (pin "6") (pinfunction "P$6_6") (pintype "bidirectional"))
    )
    (net (code "51") (name "unconnected-(U$2-P$10-Pad10)") (class "Default")
      (node (ref "U$2") (pin "10") (pinfunction "P$10_10") (pintype "bidirectional"))
    )
    (net (code "52") (name "unconnected-(U$2-P$11-Pad11)") (class "Default")
      (node (ref "U$2") (pin "11") (pinfunction "P$11_11") (pintype "bidirectional"))
    )
    (net (code "53") (name "unconnected-(U$2-P$12-Pad12)") (class "Default")
      (node (ref "U$2") (pin "12") (pinfunction "P$12_12") (pintype "bidirectional"))
    )
    (net (code "54") (name "unconnected-(U$2-P$13-Pad13)") (class "Default")
      (node (ref "U$2") (pin "13") (pinfunction "P$13_13") (pintype "bidirectional"))
    )
    (net (code "55") (name "unconnected-(U$2-P$14-Pad14)") (class "Default")
      (node (ref "U$2") (pin "14") (pinfunction "P$14_14") (pintype "bidirectional"))
    )
    (net (code "56") (name "unconnected-(U$2-P$15-Pad15)") (class "Default")
      (node (ref "U$2") (pin "15") (pinfunction "P$15_15") (pintype "bidirectional"))
    )
    (net (code "57") (name "unconnected-(U$2-P$29-Pad29)") (class "Default")
      (node (ref "U$2") (pin "29") (pinfunction "P$29_29") (pintype "bidirectional"))
    )
    (net (code "58") (name "unconnected-(U$2-P$32-Pad32)") (class "Default")
      (node (ref "U$2") (pin "32") (pinfunction "P$32_32") (pintype "bidirectional"))
    )
    (net (code "59") (name "unconnected-(U$2-P$33-Pad33)") (class "Default")
      (node (ref "U$2") (pin "33") (pinfunction "P$33_33") (pintype "bidirectional"))
    )
    (net (code "60") (name "unconnected-(U$2-P$35-Pad35)") (class "Default")
      (node (ref "U$2") (pin "35") (pinfunction "P$35_35") (pintype "bidirectional"))
    )
    (net (code "61") (name "unconnected-(U$2-P$36-Pad36)") (class "Default")
      (node (ref "U$2") (pin "36") (pinfunction "P$36_36") (pintype "bidirectional"))
    )
    (net (code "62") (name "unconnected-(U$2-P$38-Pad38)") (class "Default")
      (node (ref "U$2") (pin "38") (pinfunction "P$38_38") (pintype "bidirectional"))
    )
  )
)
